# ESC-stub.net
KiCad netlist of a schematic drawn in EAGLE
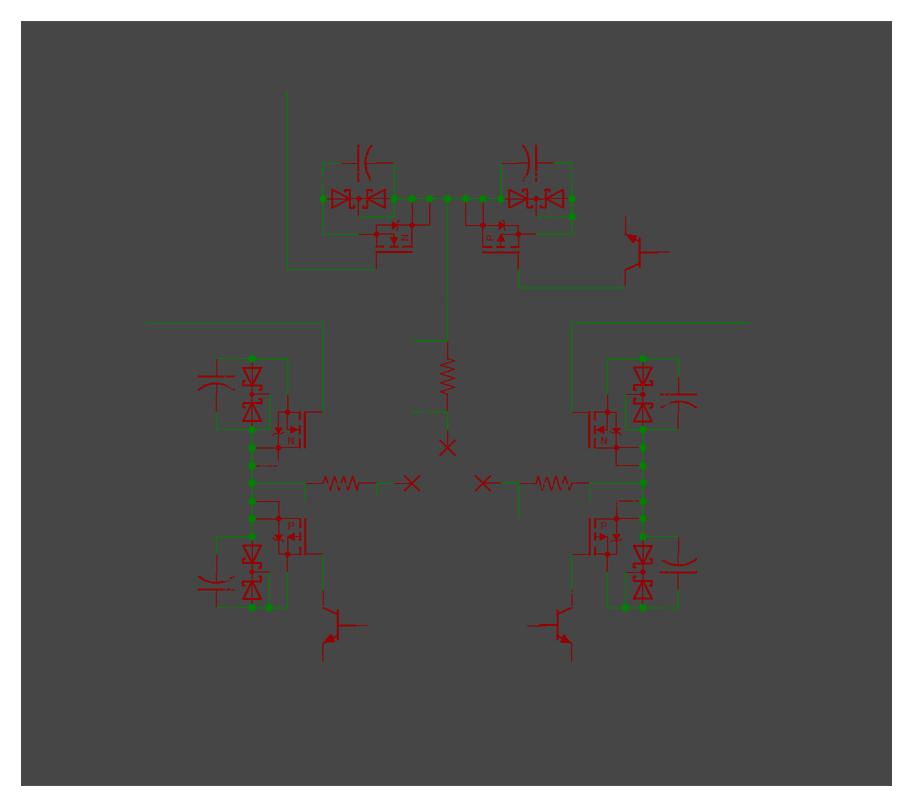
[diagram p0: schematic, sheet 1]

(export (version "E")
  (design (tool "Eeschema 10.0.6"))
  (components
    (comp (ref "C9")
      (value "C-USC0402K")
      (footprint "eagle-import:C0402K")
      (libsource (lib "eagle-import") (part "C-USC0402K"))
    )
    (comp (ref "C10")
      (value "C-USC0402K")
      (footprint "eagle-import:C0402K")
      (libsource (lib "eagle-import") (part "C-USC0402K"))
    )
    (comp (ref "C11")
      (value "C-USC0402K")
      (footprint "eagle-import:C0402K")
      (libsource (lib "eagle-import") (part "C-USC0402K"))
    )
    (comp (ref "C12")
      (value "C-USC0402K")
      (footprint "eagle-import:C0402K")
      (libsource (lib "eagle-import") (part "C-USC0402K"))
    )
    (comp (ref "C13")
      (value "C-USC0402K")
      (footprint "eagle-import:C0402K")
      (libsource (lib "eagle-import") (part "C-USC0402K"))
    )
    (comp (ref "C14")
      (value "C-USC0402K")
      (footprint "eagle-import:C0402K")
      (libsource (lib "eagle-import") (part "C-USC0402K"))
    )
    (comp (ref "D2")
      (value "BAS40-05")
      (footprint "eagle-import:SOT23")
      (libsource (lib "eagle-import") (part "BAS40-05"))
    )
    (comp (ref "D3")
      (value "BAS40-05")
      (footprint "eagle-import:SOT23")
      (libsource (lib "eagle-import") (part "BAS40-05"))
    )
    (comp (ref "D4")
      (value "BAS40-05")
      (footprint "eagle-import:SOT23")
      (libsource (lib "eagle-import") (part "BAS40-05"))
    )
    (comp (ref "D5")
      (value "BAS40-05")
      (footprint "eagle-import:SOT23")
      (libsource (lib "eagle-import") (part "BAS40-05"))
    )
    (comp (ref "D6")
      (value "BAS40-05")
      (footprint "eagle-import:SOT23")
      (libsource (lib "eagle-import") (part "BAS40-05"))
    )
    (comp (ref "D7")
      (value "BAS40-05")
      (footprint "eagle-import:SOT23")
      (libsource (lib "eagle-import") (part "BAS40-05"))
    )
    (comp (ref "PAD1")
      (value "WIREPADSMD5-2,5")
      (footprint "eagle-import:5-2,5")
      (libsource (lib "eagle-import") (part "WIREPADSMD5-2,5"))
    )
    (comp (ref "PAD2")
      (value "WIREPADSMD5-2,5")
      (footprint "eagle-import:5-2,5")
      (libsource (lib "eagle-import") (part "WIREPADSMD5-2,5"))
    )
    (comp (ref "PAD3")
      (value "WIREPADSMD5-2,5")
      (footprint "eagle-import:5-2,5")
      (libsource (lib "eagle-import") (part "WIREPADSMD5-2,5"))
    )
    (comp (ref "R2")
      (value "R-US_R2512W")
      (footprint "eagle-import:R2512W")
      (libsource (lib "eagle-import") (part "R-US_R2512W"))
    )
    (comp (ref "R3")
      (value "R-US_R2512W")
      (footprint "eagle-import:R2512W")
      (libsource (lib "eagle-import") (part "R-US_R2512W"))
    )
    (comp (ref "R4")
      (value "R-US_R2512W")
      (footprint "eagle-import:R2512W")
      (libsource (lib "eagle-import") (part "R-US_R2512W"))
    )
    (comp (ref "U$14")
      (value "IRF7309Q")
      (footprint "eagle-import:SO-8")
      (libsource (lib "eagle-import") (part "IRF7309Q"))
    )
    (comp (ref "U$16")
      (value "IRF7309Q")
      (footprint "eagle-import:SO-8")
      (libsource (lib "eagle-import") (part "IRF7309Q"))
    )
    (comp (ref "U$18")
      (value "IRF7309Q")
      (footprint "eagle-import:SO-8")
      (libsource (lib "eagle-import") (part "IRF7309Q"))
    )
    (comp (ref "U$19")
      (value "2PC4617")
      (footprint "eagle-import:SOT-416")
      (libsource (lib "eagle-import") (part "2PC4617"))
    )
    (comp (ref "U$20")
      (value "2PC4617")
      (footprint "eagle-import:SOT-416")
      (libsource (lib "eagle-import") (part "2PC4617"))
    )
    (comp (ref "U$21")
      (value "2PC4617")
      (footprint "eagle-import:SOT-416")
      (libsource (lib "eagle-import") (part "2PC4617"))
    )
  )
  (nets
    (net (code "1") (name "Net-(D2-A1)") (class "Default")
      (node (ref "C10") (pin "2") (pinfunction "2_2") (pintype "passive"))
      (node (ref "C9") (pin "2") (pinfunction "2_2") (pintype "passive"))
      (node (ref "D2") (pin "1") (pinfunction "A1_1") (pintype "passive"))
      (node (ref "D2") (pin "3") (pinfunction "C_3") (pintype "passive"))
      (node (ref "D3") (pin "1") (pinfunction "A1_1") (pintype "passive"))
      (node (ref "R2") (pin "1") (pinfunction "1_1") (pintype "passive"))
      (node (ref "U$14") (pin "5") (pinfunction "P-D$1_5") (pintype "passive"))
      (node (ref "U$14") (pin "6") (pinfunction "P-D$2_6") (pintype "passive"))
      (node (ref "U$14") (pin "7") (pinfunction "N-D$2_7") (pintype "passive"))
      (node (ref "U$14") (pin "8") (pinfunction "N-D$1_8") (pintype "passive"))
    )
    (net (code "2") (name "Net-(D2-A2)") (class "Default")
      (node (ref "C9") (pin "1") (pinfunction "1_1") (pintype "passive"))
      (node (ref "D2") (pin "2") (pinfunction "A2_2") (pintype "passive"))
      (node (ref "U$14") (pin "1") (pinfunction "N-S_1") (pintype "passive"))
    )
    (net (code "3") (name "Net-(D3-A2)") (class "Default")
      (node (ref "C10") (pin "1") (pinfunction "1_1") (pintype "passive"))
      (node (ref "D3") (pin "2") (pinfunction "A2_2") (pintype "passive"))
      (node (ref "D3") (pin "3") (pinfunction "C_3") (pintype "passive"))
      (node (ref "U$14") (pin "3") (pinfunction "P-S_3") (pintype "passive"))
    )
    (net (code "4") (name "Net-(D4-A1)") (class "Default")
      (node (ref "C11") (pin "2") (pinfunction "2_2") (pintype "passive"))
      (node (ref "C12") (pin "2") (pinfunction "2_2") (pintype "passive"))
      (node (ref "D4") (pin "1") (pinfunction "A1_1") (pintype "passive"))
      (node (ref "D4") (pin "3") (pinfunction "C_3") (pintype "passive"))
      (node (ref "D5") (pin "1") (pinfunction "A1_1") (pintype "passive"))
      (node (ref "R3") (pin "2") (pinfunction "2_2") (pintype "passive"))
      (node (ref "U$16") (pin "5") (pinfunction "P-D$1_5") (pintype "passive"))
      (node (ref "U$16") (pin "6") (pinfunction "P-D$2_6") (pintype "passive"))
      (node (ref "U$16") (pin "7") (pinfunction "N-D$2_7") (pintype "passive"))
      (node (ref "U$16") (pin "8") (pinfunction "N-D$1_8") (pintype "passive"))
    )
    (net (code "5") (name "Net-(D4-A2)") (class "Default")
      (node (ref "C11") (pin "1") (pinfunction "1_1") (pintype "passive"))
      (node (ref "D4") (pin "2") (pinfunction "A2_2") (pintype "passive"))
      (node (ref "U$16") (pin "1") (pinfunction "N-S_1") (pintype "passive"))
    )
    (net (code "6") (name "Net-(D5-A2)") (class "Default")
      (node (ref "C12") (pin "1") (pinfunction "1_1") (pintype "passive"))
      (node (ref "D5") (pin "2") (pinfunction "A2_2") (pintype "passive"))
      (node (ref "D5") (pin "3") (pinfunction "C_3") (pintype "passive"))
      (node (ref "U$16") (pin "3") (pinfunction "P-S_3") (pintype "passive"))
    )
    (net (code "7") (name "Net-(D6-A1)") (class "Default")
      (node (ref "C13") (pin "2") (pinfunction "2_2") (pintype "passive"))
      (node (ref "C14") (pin "2") (pinfunction "2_2") (pintype "passive"))
      (node (ref "D6") (pin "1") (pinfunction "A1_1") (pintype "passive"))
      (node (ref "D6") (pin "3") (pinfunction "C_3") (pintype "passive"))
      (node (ref "D7") (pin "1") (pinfunction "A1_1") (pintype "passive"))
      (node (ref "R4") (pin "1") (pinfunction "1_1") (pintype "passive"))
      (node (ref "U$18") (pin "5") (pinfunction "P-D$1_5") (pintype "passive"))
      (node (ref "U$18") (pin "6") (pinfunction "P-D$2_6") (pintype "passive"))
      (node (ref "U$18") (pin "7") (pinfunction "N-D$2_7") (pintype "passive"))
      (node (ref "U$18") (pin "8") (pinfunction "N-D$1_8") (pintype "passive"))
    )
    (net (code "8") (name "Net-(D6-A2)") (class "Default")
      (node (ref "C13") (pin "1") (pinfunction "1_1") (pintype "passive"))
      (node (ref "D6") (pin "2") (pinfunction "A2_2") (pintype "passive"))
      (node (ref "U$18") (pin "1") (pinfunction "N-S_1") (pintype "passive"))
    )
    (net (code "9") (name "Net-(D7-A2)") (class "Default")
      (node (ref "C14") (pin "1") (pinfunction "1_1") (pintype "passive"))
      (node (ref "D7") (pin "2") (pinfunction "A2_2") (pintype "passive"))
      (node (ref "D7") (pin "3") (pinfunction "C_3") (pintype "passive"))
      (node (ref "U$18") (pin "3") (pinfunction "P-S_3") (pintype "passive"))
    )
    (net (code "10") (name "Net-(PAD1-P)") (class "Default")
      (node (ref "PAD1") (pin "1") (pinfunction "P_1") (pintype "passive"))
      (node (ref "R2") (pin "2") (pinfunction "2_2") (pintype "passive"))
    )
    (net (code "11") (name "Net-(PAD2-P)") (class "Default")
      (node (ref "PAD2") (pin "1") (pinfunction "P_1") (pintype "passive"))
      (node (ref "R3") (pin "1") (pinfunction "1_1") (pintype "passive"))
    )
    (net (code "12") (name "Net-(PAD3-P)") (class "Default")
      (node (ref "PAD3") (pin "1") (pinfunction "P_1") (pintype "passive"))
      (node (ref "R4") (pin "2") (pinfunction "2_2") (pintype "passive"))
    )
    (net (code "13") (name "Net-(U$14-P-G)") (class "Default")
      (node (ref "U$14") (pin "4") (pinfunction "P-G_4") (pintype "passive"))
      (node (ref "U$19") (pin "P$3") (pinfunction "P$3_P$3") (pintype "input"))
    )
    (net (code "14") (name "Net-(U$16-P-G)") (class "Default")
      (node (ref "U$16") (pin "4") (pinfunction "P-G_4") (pintype "passive"))
      (node (ref "U$20") (pin "P$3") (pinfunction "P$3_P$3") (pintype "input"))
    )
    (net (code "15") (name "Net-(U$18-P-G)") (class "Default")
      (node (ref "U$18") (pin "4") (pinfunction "P-G_4") (pintype "passive"))
      (node (ref "U$21") (pin "P$3") (pinfunction "P$3_P$3") (pintype "input"))
    )
    (net (code "16") (name "unconnected-(U$14-N-G-Pad2)") (class "Default")
      (node (ref "U$14") (pin "2") (pinfunction "N-G_2") (pintype "passive"))
    )
    (net (code "17") (name "unconnected-(U$16-N-G-Pad2)") (class "Default")
      (node (ref "U$16") (pin "2") (pinfunction "N-G_2") (pintype "passive"))
    )
    (net (code "18") (name "unconnected-(U$18-N-G-Pad2)") (class "Default")
      (node (ref "U$18") (pin "2") (pinfunction "N-G_2") (pintype "passive"))
    )
    (net (code "19") (name "unconnected-(U$19-PadP$1)") (class "Default")
      (node (ref "U$19") (pin "P$1") (pinfunction "P$1_P$1") (pintype "input"))
    )
    (net (code "20") (name "unconnected-(U$19-PadP$2)") (class "Default")
      (node (ref "U$19") (pin "P$2") (pinfunction "P$2_P$2") (pintype "output"))
    )
    (net (code "21") (name "unconnected-(U$20-PadP$1)") (class "Default")
      (node (ref "U$20") (pin "P$1") (pinfunction "P$1_P$1") (pintype "input"))
    )
    (net (code "22") (name "unconnected-(U$20-PadP$2)") (class "Default")
      (node (ref "U$20") (pin "P$2") (pinfunction "P$2_P$2") (pintype "output"))
    )
    (net (code "23") (name "unconnected-(U$21-PadP$1)") (class "Default")
      (node (ref "U$21") (pin "P$1") (pinfunction "P$1_P$1") (pintype "input"))
    )
    (net (code "24") (name "unconnected-(U$21-PadP$2)") (class "Default")
      (node (ref "U$21") (pin "P$2") (pinfunction "P$2_P$2") (pintype "output"))
    )
  )
)
